# mainboard.net
KiCad netlist of a schematic drawn in EAGLE
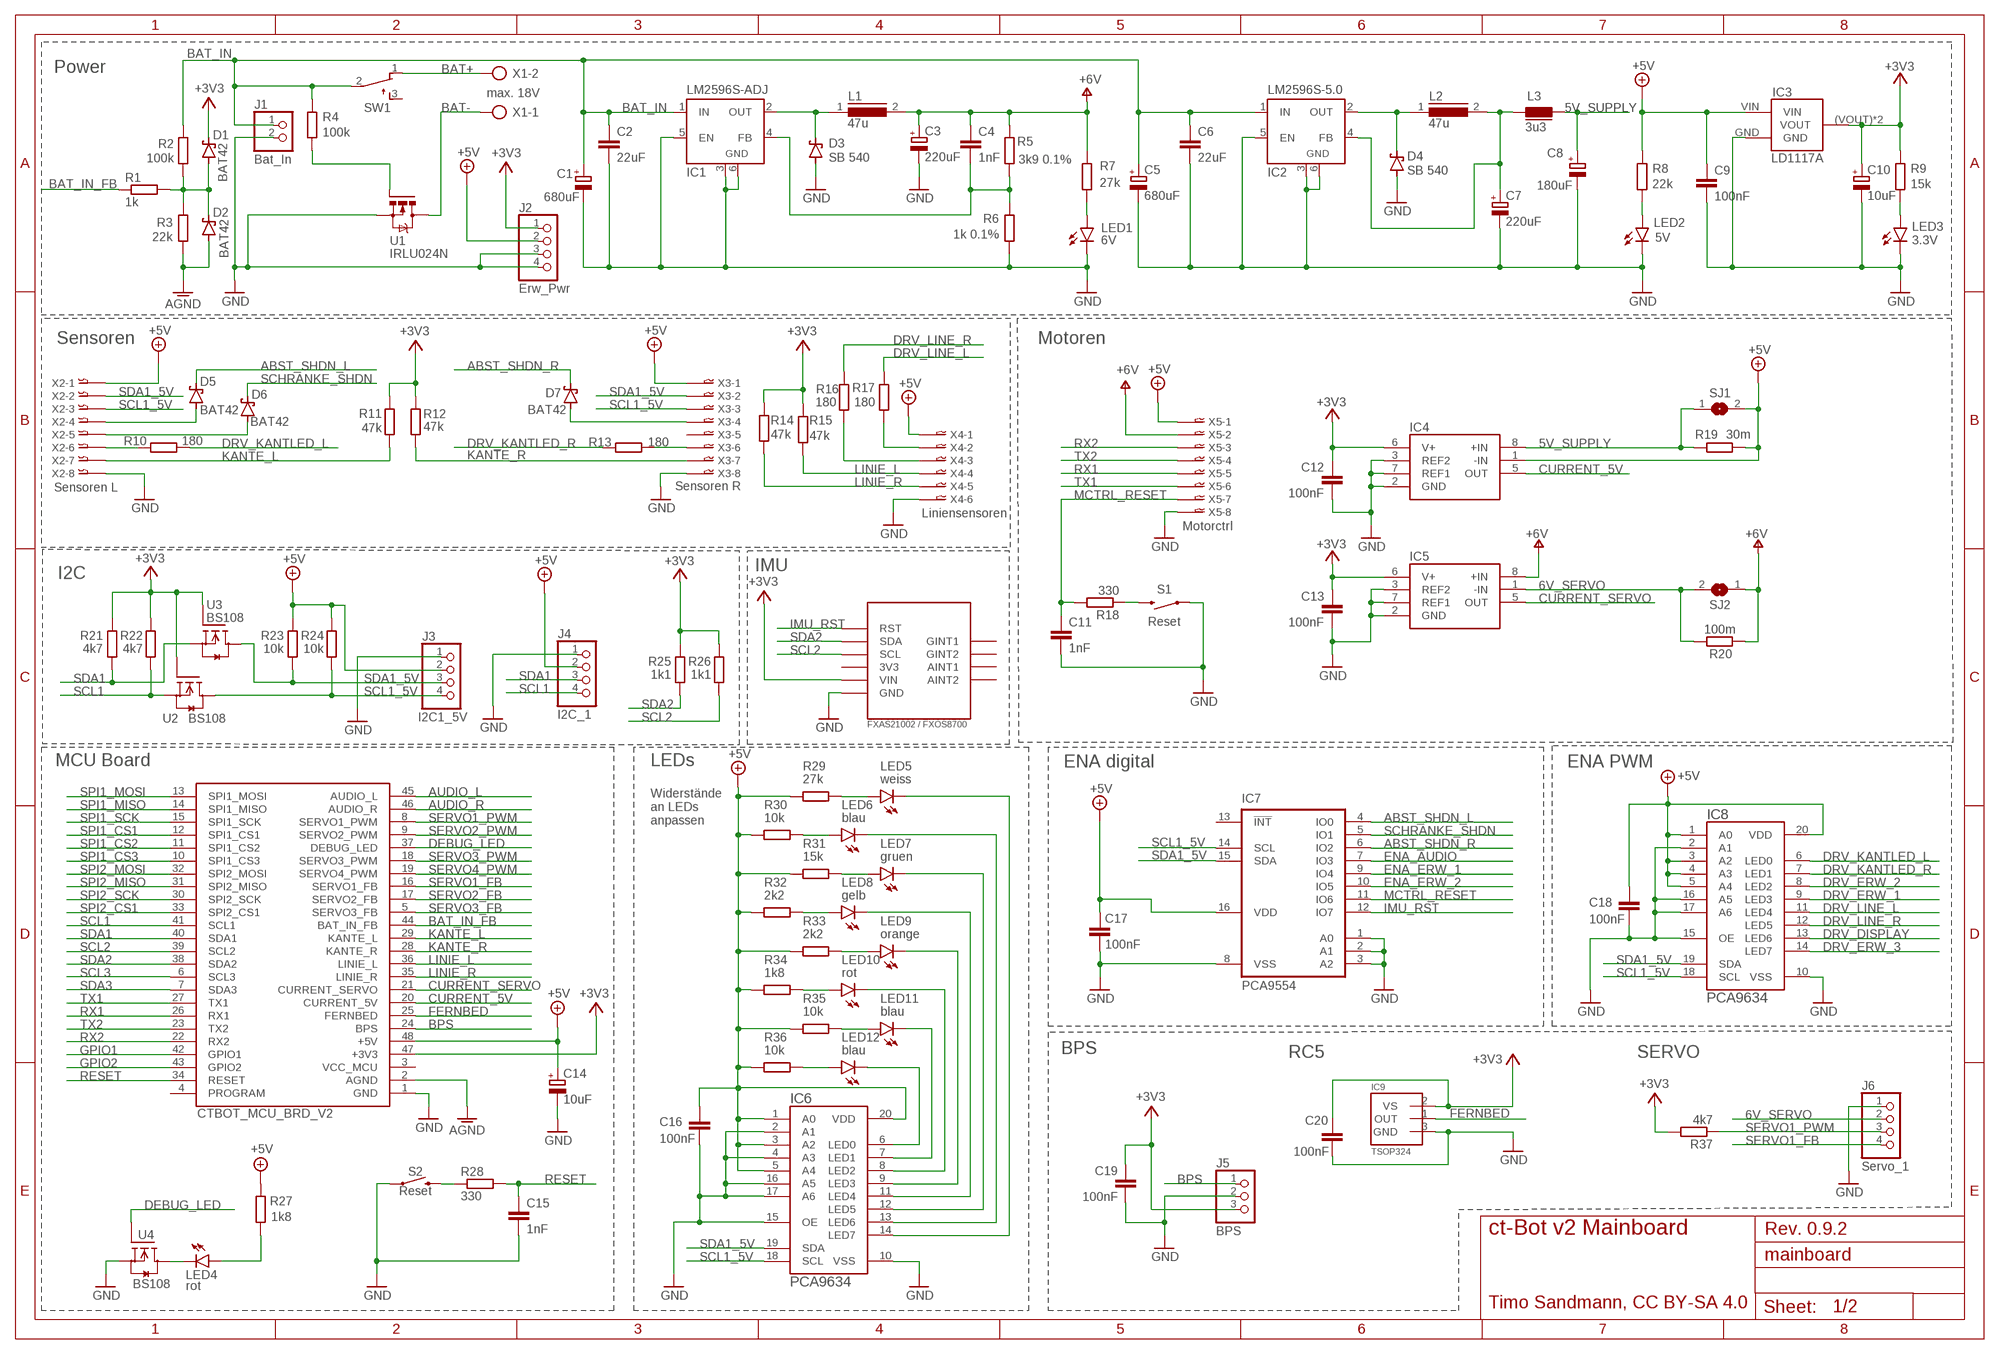
[diagram p0: schematic, sheet 1]
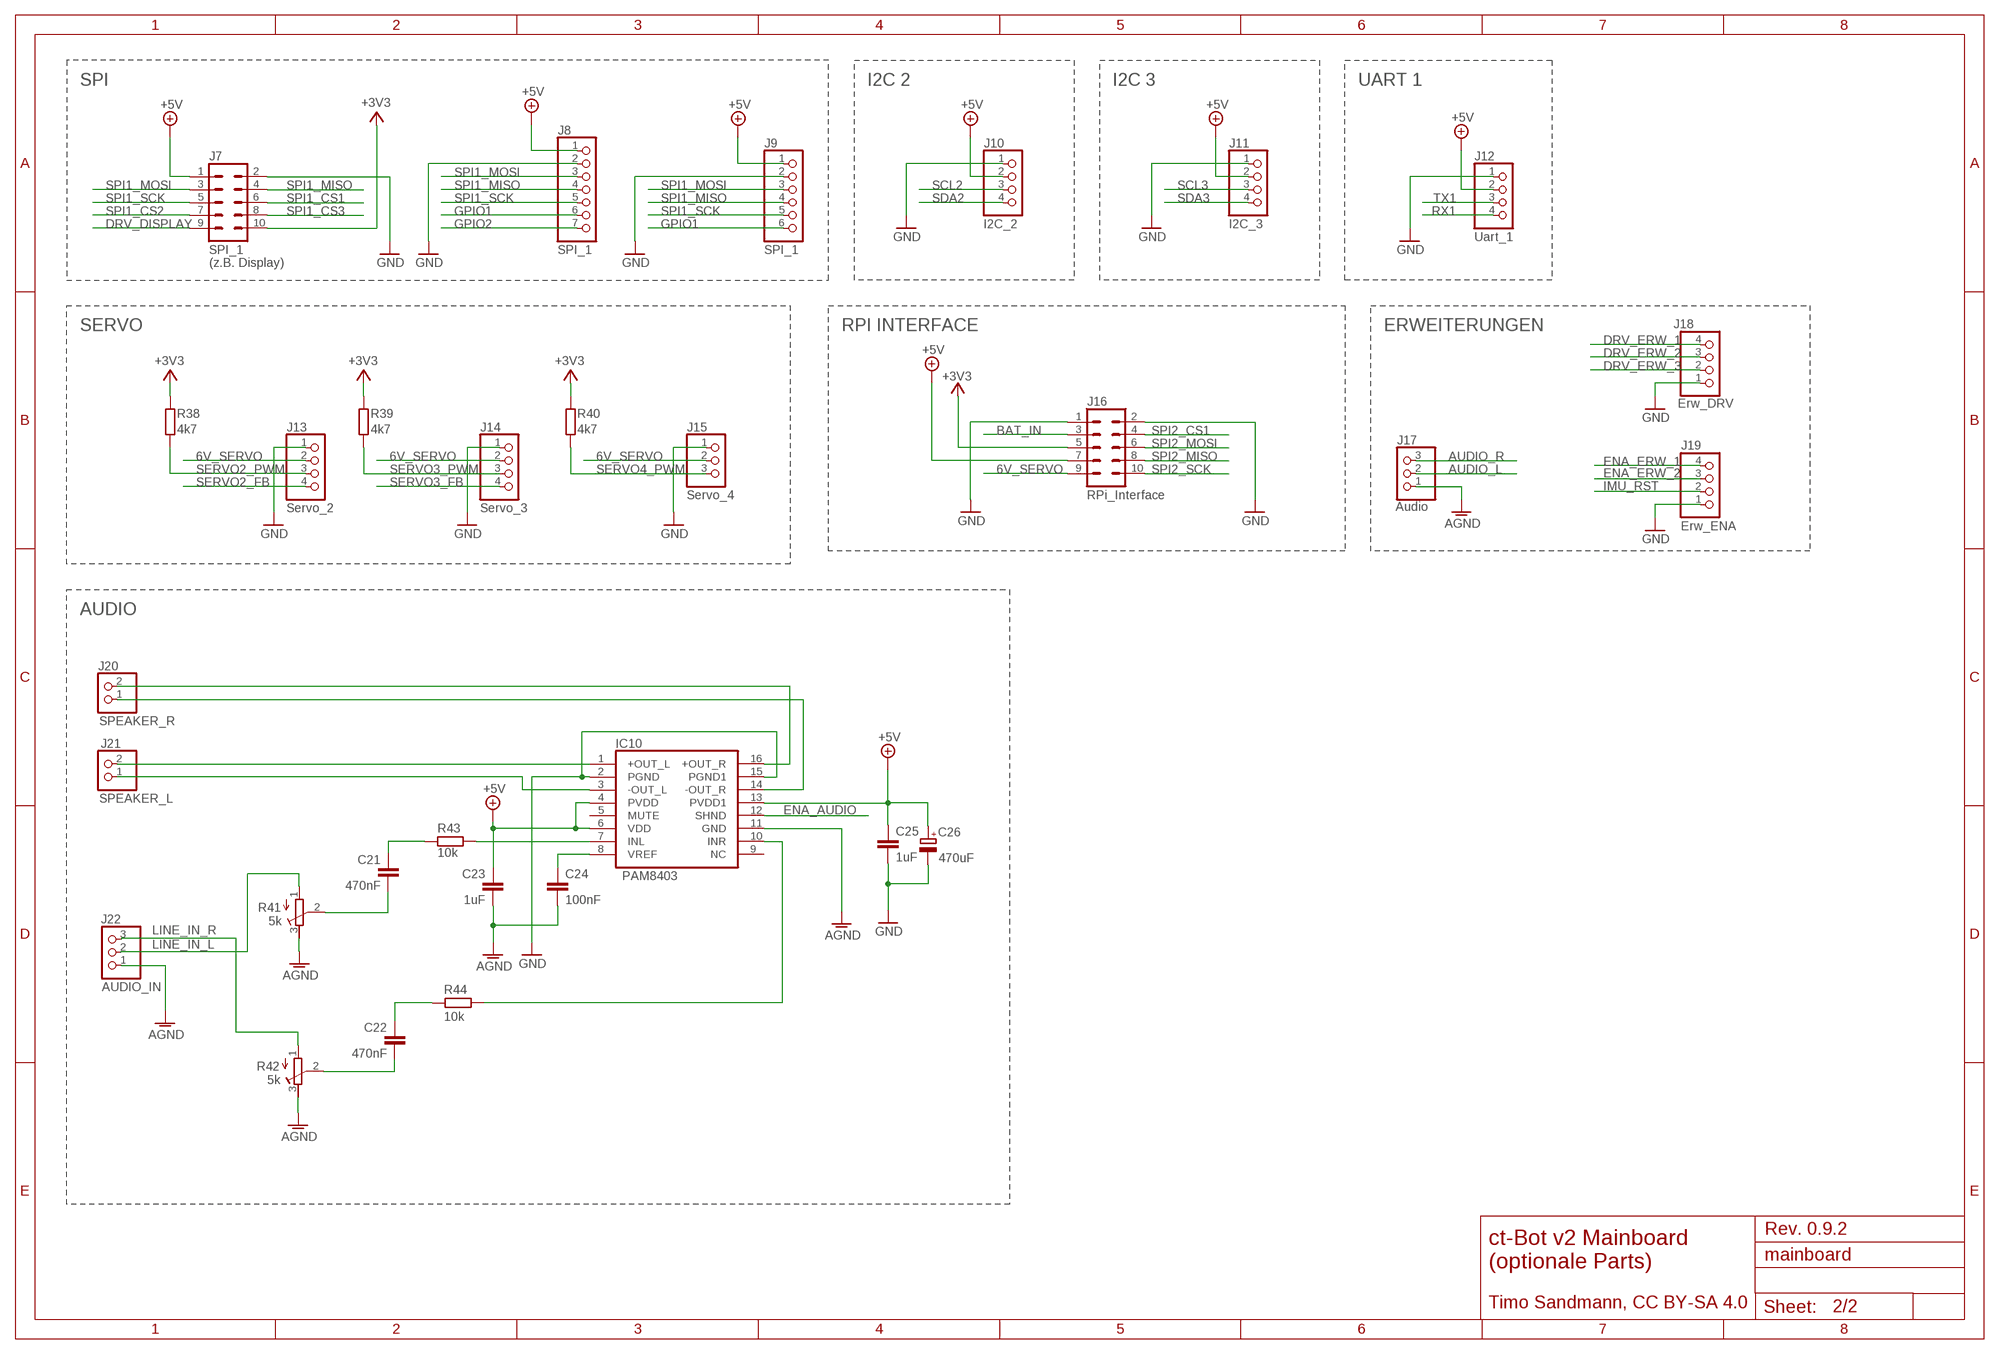
[diagram p1: schematic, sheet 2]

(export (version "E")
  (design (tool "Eeschema 10.0.6"))
  (components
    (comp (ref "C21")
      (value "470nF")
      (footprint "eagle-import:C025-025X050")
      (libsource (lib "eagle-import") (part "C-EU025-025X050"))
    )
    (comp (ref "C22")
      (value "470nF")
      (footprint "eagle-import:C025-025X050")
      (libsource (lib "eagle-import") (part "C-EU025-025X050"))
    )
    (comp (ref "C23")
      (value "1uF")
      (footprint "eagle-import:C025-025X050")
      (libsource (lib "eagle-import") (part "C-EU025-025X050"))
    )
    (comp (ref "C24")
      (value "100nF")
      (footprint "eagle-import:C025-025X050")
      (libsource (lib "eagle-import") (part "C-EU025-025X050"))
    )
    (comp (ref "C25")
      (value "1uF")
      (footprint "eagle-import:C025-025X050")
      (libsource (lib "eagle-import") (part "C-EU025-025X050"))
    )
    (comp (ref "C26")
      (value "470uF")
      (footprint "eagle-import:E3,5-8")
      (libsource (lib "eagle-import") (part "CPOL-EUE3.5-8"))
    )
    (comp (ref "IC10")
      (value "PAM8403")
      (footprint "eagle-import:SOP-16")
      (libsource (lib "eagle-import") (part "PAM8403"))
    )
    (comp (ref "J7")
      (value "SPI_1")
      (footprint "eagle-import:ML10")
      (libsource (lib "eagle-import") (part "ML10"))
    )
    (comp (ref "J8")
      (value "SPI_1")
      (footprint "eagle-import:1X07")
      (libsource (lib "eagle-import") (part "PINHD-1X7"))
    )
    (comp (ref "J9")
      (value "SPI_1")
      (footprint "eagle-import:1X06")
      (libsource (lib "eagle-import") (part "PINHD-1X6"))
    )
    (comp (ref "J10")
      (value "I2C_2")
      (footprint "eagle-import:1X04")
      (libsource (lib "eagle-import") (part "PINHD-1X4"))
    )
    (comp (ref "J11")
      (value "I2C_3")
      (footprint "eagle-import:1X04")
      (libsource (lib "eagle-import") (part "PINHD-1X4"))
    )
    (comp (ref "J12")
      (value "Uart_1")
      (footprint "eagle-import:1X04")
      (libsource (lib "eagle-import") (part "PINHD-1X4"))
    )
    (comp (ref "J13")
      (value "Servo_2")
      (footprint "eagle-import:1X04")
      (libsource (lib "eagle-import") (part "PINHD-1X4"))
    )
    (comp (ref "J14")
      (value "Servo_3")
      (footprint "eagle-import:1X04")
      (libsource (lib "eagle-import") (part "PINHD-1X4"))
    )
    (comp (ref "J15")
      (value "Servo_4")
      (footprint "eagle-import:1X03")
      (libsource (lib "eagle-import") (part "PINHD-1X3"))
    )
    (comp (ref "J16")
      (value "RPi_Interface")
      (footprint "eagle-import:ML10")
      (libsource (lib "eagle-import") (part "ML10"))
    )
    (comp (ref "J17")
      (value "Audio")
      (footprint "eagle-import:1X03")
      (libsource (lib "eagle-import") (part "PINHD-1X3"))
    )
    (comp (ref "J18")
      (value "Erw_DRV")
      (footprint "eagle-import:1X04")
      (libsource (lib "eagle-import") (part "PINHD-1X4"))
    )
    (comp (ref "J19")
      (value "Erw_ENA")
      (footprint "eagle-import:1X04")
      (libsource (lib "eagle-import") (part "PINHD-1X4"))
    )
    (comp (ref "J20")
      (value "SPEAKER_R")
      (footprint "eagle-import:1X02")
      (libsource (lib "eagle-import") (part "PINHD-1X2"))
    )
    (comp (ref "J21")
      (value "SPEAKER_L")
      (footprint "eagle-import:1X02")
      (libsource (lib "eagle-import") (part "PINHD-1X2"))
    )
    (comp (ref "J22")
      (value "AUDIO_IN")
      (footprint "eagle-import:1X03")
      (libsource (lib "eagle-import") (part "PINHD-1X3"))
    )
    (comp (ref "R38")
      (value "4k7")
      (footprint "eagle-import:0204_7")
      (libsource (lib "eagle-import") (part "R-EU_0204/7"))
    )
    (comp (ref "R39")
      (value "4k7")
      (footprint "eagle-import:0204_7")
      (libsource (lib "eagle-import") (part "R-EU_0204/7"))
    )
    (comp (ref "R40")
      (value "4k7")
      (footprint "eagle-import:0204_7")
      (libsource (lib "eagle-import") (part "R-EU_0204/7"))
    )
    (comp (ref "R41")
      (value "5k")
      (footprint "eagle-import:RTRIM64W")
      (libsource (lib "eagle-import") (part "R-TRIMM64W"))
    )
    (comp (ref "R42")
      (value "5k")
      (footprint "eagle-import:RTRIM64W")
      (libsource (lib "eagle-import") (part "R-TRIMM64W"))
    )
    (comp (ref "R43")
      (value "10k")
      (footprint "eagle-import:0204V")
      (libsource (lib "eagle-import") (part "R-EU_0204/2V"))
    )
    (comp (ref "R44")
      (value "10k")
      (footprint "eagle-import:0204V")
      (libsource (lib "eagle-import") (part "R-EU_0204/2V"))
    )
    (comp (ref "C1")
      (value "680uF")
      (footprint "eagle-import:E5-10,5")
      (libsource (lib "eagle-import") (part "CPOL-EUE5-10.5"))
    )
    (comp (ref "C2")
      (value "22uF")
      (footprint "eagle-import:C025-025X050")
      (libsource (lib "eagle-import") (part "C-EU025-025X050"))
    )
    (comp (ref "C3")
      (value "220uF")
      (footprint "eagle-import:E5-10,5")
      (libsource (lib "eagle-import") (part "CPOL-EUE5-10.5"))
    )
    (comp (ref "C4")
      (value "1nF")
      (footprint "eagle-import:C025-025X050")
      (libsource (lib "eagle-import") (part "C-EU025-025X050"))
    )
    (comp (ref "C5")
      (value "680uF")
      (footprint "eagle-import:E5-10,5")
      (libsource (lib "eagle-import") (part "CPOL-EUE5-10.5"))
    )
    (comp (ref "C6")
      (value "22uF")
      (footprint "eagle-import:C025-025X050")
      (libsource (lib "eagle-import") (part "C-EU025-025X050"))
    )
    (comp (ref "C7")
      (value "220uF")
      (footprint "eagle-import:E5-10,5")
      (libsource (lib "eagle-import") (part "CPOL-EUE5-10.5"))
    )
    (comp (ref "C8")
      (value "180uF")
      (footprint "eagle-import:E3,5-8")
      (libsource (lib "eagle-import") (part "CPOL-EUE3.5-8"))
    )
    (comp (ref "C9")
      (value "100nF")
      (footprint "eagle-import:C025-025X050")
      (libsource (lib "eagle-import") (part "C-EU025-025X050"))
    )
    (comp (ref "C10")
      (value "10uF")
      (footprint "eagle-import:E2-5")
      (libsource (lib "eagle-import") (part "CPOL-EUE2-5"))
    )
    (comp (ref "C11")
      (value "1nF")
      (footprint "eagle-import:C025-025X050")
      (libsource (lib "eagle-import") (part "C-EU025-025X050"))
    )
    (comp (ref "C12")
      (value "100nF")
      (footprint "eagle-import:C0805")
      (libsource (lib "eagle-import") (part "C-EUC0805"))
    )
    (comp (ref "C13")
      (value "100nF")
      (footprint "eagle-import:C0805")
      (libsource (lib "eagle-import") (part "C-EUC0805"))
    )
    (comp (ref "C14")
      (value "10uF")
      (footprint "eagle-import:TT2D5L")
      (libsource (lib "eagle-import") (part "CPOL-EUTT2D5L"))
    )
    (comp (ref "C15")
      (value "1nF")
      (footprint "eagle-import:C025-025X050")
      (libsource (lib "eagle-import") (part "C-EU025-025X050"))
    )
    (comp (ref "C16")
      (value "100nF")
      (footprint "eagle-import:C025-025X050")
      (libsource (lib "eagle-import") (part "C-EU025-025X050"))
    )
    (comp (ref "C17")
      (value "100nF")
      (footprint "eagle-import:C025-025X050")
      (libsource (lib "eagle-import") (part "C-EU025-025X050"))
    )
    (comp (ref "C18")
      (value "100nF")
      (footprint "eagle-import:C025-025X050")
      (libsource (lib "eagle-import") (part "C-EU025-025X050"))
    )
    (comp (ref "C19")
      (value "100nF")
      (footprint "eagle-import:C025-025X050")
      (libsource (lib "eagle-import") (part "C-EU025-025X050"))
    )
    (comp (ref "C20")
      (value "100nF")
      (footprint "eagle-import:C025-025X050")
      (libsource (lib "eagle-import") (part "C-EU025-025X050"))
    )
    (comp (ref "D1")
      (value "BAT42")
      (footprint "eagle-import:DO35-7")
      (libsource (lib "eagle-import") (part "BAT42DO35-7"))
    )
    (comp (ref "D2")
      (value "BAT42")
      (footprint "eagle-import:DO35-7")
      (libsource (lib "eagle-import") (part "BAT42DO35-7"))
    )
    (comp (ref "D3")
      (value "SB 540")
      (footprint "eagle-import:DO201T15")
      (libsource (lib "eagle-import") (part "SCHOTTKY-DIODEDO201T15"))
    )
    (comp (ref "D4")
      (value "SB 540")
      (footprint "eagle-import:DO201T15")
      (libsource (lib "eagle-import") (part "SCHOTTKY-DIODEDO201T15"))
    )
    (comp (ref "D5")
      (value "BAT42")
      (footprint "eagle-import:0207_2V")
      (libsource (lib "eagle-import") (part "BAT42{dblquote}"))
    )
    (comp (ref "D6")
      (value "BAT42")
      (footprint "eagle-import:0207_2V")
      (libsource (lib "eagle-import") (part "BAT42{dblquote}"))
    )
    (comp (ref "D7")
      (value "BAT42")
      (footprint "eagle-import:0207_2V")
      (libsource (lib "eagle-import") (part "BAT42{dblquote}"))
    )
    (comp (ref "IC1")
      (value "LM2596S-ADJ")
      (footprint "eagle-import:TO263-5")
      (libsource (lib "eagle-import") (part "LM2596S"))
    )
    (comp (ref "IC2")
      (value "LM2596S-5.0")
      (footprint "eagle-import:TO263-5")
      (libsource (lib "eagle-import") (part "LM2596S"))
    )
    (comp (ref "IC3")
      (value "LD1117A")
      (footprint "eagle-import:LD1117SOT-223")
      (libsource (lib "eagle-import") (part "LD1117"))
    )
    (comp (ref "IC4")
      (value "INA28AID")
      (footprint "eagle-import:SO08")
      (fields (field (name "MF") "TEXAS INSTRUMENTS"))
      (libsource (lib "eagle-import") (part "INA28AID"))
    )
    (comp (ref "IC5")
      (value "INA28AID")
      (footprint "eagle-import:SO08")
      (fields (field (name "MF") "TEXAS INSTRUMENTS"))
      (libsource (lib "eagle-import") (part "INA28AID"))
    )
    (comp (ref "IC6")
      (value "PCA9634")
      (footprint "eagle-import:SO20W")
      (libsource (lib "eagle-import") (part "PCA9634-SO20"))
    )
    (comp (ref "IC7")
      (value "PCA9554")
      (footprint "eagle-import:SO16W")
      (libsource (lib "eagle-import") (part "PCA9554D"))
    )
    (comp (ref "IC8")
      (value "PCA9634")
      (footprint "eagle-import:SO20W")
      (libsource (lib "eagle-import") (part "PCA9634-SO20"))
    )
    (comp (ref "IC9")
      (value "TSOP324")
      (footprint "eagle-import:TSOP324")
      (libsource (lib "eagle-import") (part "TSOP324"))
    )
    (comp (ref "J1")
      (value "Bat_In")
      (footprint "eagle-import:1X02")
      (libsource (lib "eagle-import") (part "PINHD-1X2"))
    )
    (comp (ref "J2")
      (value "Erw_Pwr")
      (footprint "eagle-import:1X04")
      (libsource (lib "eagle-import") (part "PINHD-1X4"))
    )
    (comp (ref "J3")
      (value "I2C1_5V")
      (footprint "eagle-import:1X04")
      (libsource (lib "eagle-import") (part "PINHD-1X4"))
    )
    (comp (ref "J4")
      (value "I2C_1")
      (footprint "eagle-import:1X04")
      (libsource (lib "eagle-import") (part "PINHD-1X4"))
    )
    (comp (ref "J5")
      (value "BPS")
      (footprint "eagle-import:1X03")
      (libsource (lib "eagle-import") (part "PINHD-1X3"))
    )
    (comp (ref "J6")
      (value "Servo_1")
      (footprint "eagle-import:1X04")
      (libsource (lib "eagle-import") (part "PINHD-1X4"))
    )
    (comp (ref "L1")
      (value "47u")
      (footprint "eagle-import:09HCP")
      (libsource (lib "eagle-import") (part "INDUCTOR_09HCP"))
    )
    (comp (ref "L2")
      (value "47u")
      (footprint "eagle-import:09HCP")
      (libsource (lib "eagle-import") (part "INDUCTOR_09HCP"))
    )
    (comp (ref "L3")
      (value "3u3")
      (footprint "eagle-import:FASTRON_07HCP_INDUCTOR")
      (libsource (lib "eagle-import") (part "07HCP-3U3"))
    )
    (comp (ref "LED1")
      (value "6V")
      (footprint "eagle-import:LED3MM")
      (libsource (lib "eagle-import") (part "LED3MM"))
    )
    (comp (ref "LED2")
      (value "5V")
      (footprint "eagle-import:LED3MM")
      (libsource (lib "eagle-import") (part "LED3MM"))
    )
    (comp (ref "LED3")
      (value "3.3V")
      (footprint "eagle-import:LED3MM")
      (libsource (lib "eagle-import") (part "LED3MM"))
    )
    (comp (ref "LED4")
      (value "rot")
      (footprint "eagle-import:LED3MM")
      (libsource (lib "eagle-import") (part "LED3MM"))
    )
    (comp (ref "LED5")
      (value "weiss")
      (footprint "eagle-import:LED3MM")
      (libsource (lib "eagle-import") (part "LED3MM"))
    )
    (comp (ref "LED6")
      (value "blau")
      (footprint "eagle-import:LED3MM")
      (libsource (lib "eagle-import") (part "LED3MM"))
    )
    (comp (ref "LED7")
      (value "gruen")
      (footprint "eagle-import:LED3MM")
      (libsource (lib "eagle-import") (part "LED3MM"))
    )
    (comp (ref "LED8")
      (value "gelb")
      (footprint "eagle-import:LED3MM")
      (libsource (lib "eagle-import") (part "LED3MM"))
    )
    (comp (ref "LED9")
      (value "orange")
      (footprint "eagle-import:LED3MM")
      (libsource (lib "eagle-import") (part "LED3MM"))
    )
    (comp (ref "LED10")
      (value "rot")
      (footprint "eagle-import:LED3MM")
      (libsource (lib "eagle-import") (part "LED3MM"))
    )
    (comp (ref "LED11")
      (value "blau")
      (footprint "eagle-import:LED3MM")
      (libsource (lib "eagle-import") (part "LED3MM"))
    )
    (comp (ref "LED12")
      (value "blau")
      (footprint "eagle-import:LED3MM")
      (libsource (lib "eagle-import") (part "LED3MM"))
    )
    (comp (ref "MCU")
      (value "CTBOT_MCU_BRD_V2")
      (footprint "eagle-import:DIP48")
      (libsource (lib "eagle-import") (part "CTBOT_MCU_BRD_V2"))
    )
    (comp (ref "R1")
      (value "1k")
      (footprint "eagle-import:0204_7")
      (libsource (lib "eagle-import") (part "R-EU_0204/7"))
    )
    (comp (ref "R2")
      (value "100k")
      (footprint "eagle-import:0204_7")
      (libsource (lib "eagle-import") (part "R-EU_0204/7"))
    )
    (comp (ref "R3")
      (value "22k")
      (footprint "eagle-import:0204_7")
      (libsource (lib "eagle-import") (part "R-EU_0204/7"))
    )
    (comp (ref "R4")
      (value "100k")
      (footprint "eagle-import:0204V")
      (libsource (lib "eagle-import") (part "R-EU_0204/2V"))
    )
    (comp (ref "R5")
      (value "3k9 0.1%")
      (footprint "eagle-import:0204V")
      (libsource (lib "eagle-import") (part "R-EU_0204/2V"))
    )
    (comp (ref "R6")
      (value "1k 0.1%")
      (footprint "eagle-import:0204V")
      (libsource (lib "eagle-import") (part "R-EU_0204/2V"))
    )
    (comp (ref "R7")
      (value "27k")
      (footprint "eagle-import:0204V")
      (libsource (lib "eagle-import") (part "R-EU_0204/2V"))
    )
    (comp (ref "R8")
      (value "22k")
      (footprint "eagle-import:0204V")
      (libsource (lib "eagle-import") (part "R-EU_0204/2V"))
    )
    (comp (ref "R9")
      (value "15k")
      (footprint "eagle-import:0204V")
      (libsource (lib "eagle-import") (part "R-EU_0204/2V"))
    )
    (comp (ref "R10")
      (value "180")
      (footprint "eagle-import:0204V")
      (libsource (lib "eagle-import") (part "R-EU_0204/2V"))
    )
    (comp (ref "R11")
      (value "47k")
      (footprint "eagle-import:0204V")
      (libsource (lib "eagle-import") (part "R-EU_0204/2V"))
    )
    (comp (ref "R12")
      (value "47k")
      (footprint "eagle-import:0204V")
      (libsource (lib "eagle-import") (part "R-EU_0204/2V"))
    )
    (comp (ref "R13")
      (value "180")
      (footprint "eagle-import:0204V")
      (libsource (lib "eagle-import") (part "R-EU_0204/2V"))
    )
    (comp (ref "R14")
      (value "47k")
      (footprint "eagle-import:0204_7")
      (libsource (lib "eagle-import") (part "R-EU_0204/7"))
    )
    (comp (ref "R15")
      (value "47k")
      (footprint "eagle-import:0204_7")
      (libsource (lib "eagle-import") (part "R-EU_0204/7"))
    )
    (comp (ref "R16")
      (value "180")
      (footprint "eagle-import:0204V")
      (libsource (lib "eagle-import") (part "R-EU_0204/2V"))
    )
    (comp (ref "R17")
      (value "180")
      (footprint "eagle-import:0204V")
      (libsource (lib "eagle-import") (part "R-EU_0204/2V"))
    )
    (comp (ref "R18")
      (value "330")
      (footprint "eagle-import:0204V")
      (libsource (lib "eagle-import") (part "R-EU_0204/2V"))
    )
    (comp (ref "R19")
      (value "30m")
      (footprint "eagle-import:R2512")
      (libsource (lib "eagle-import") (part "R-EU_R2512"))
    )
    (comp (ref "R20")
      (value "100m")
      (footprint "eagle-import:R2512")
      (libsource (lib "eagle-import") (part "R-EU_R2512"))
    )
    (comp (ref "R21")
      (value "4k7")
      (footprint "eagle-import:0204_7")
      (libsource (lib "eagle-import") (part "R-EU_0204/7"))
    )
    (comp (ref "R22")
      (value "4k7")
      (footprint "eagle-import:0204_7")
      (libsource (lib "eagle-import") (part "R-EU_0204/7"))
    )
    (comp (ref "R23")
      (value "10k")
      (footprint "eagle-import:0204V")
      (libsource (lib "eagle-import") (part "R-EU_0204/2V"))
    )
    (comp (ref "R24")
      (value "10k")
      (footprint "eagle-import:0204V")
      (libsource (lib "eagle-import") (part "R-EU_0204/2V"))
    )
    (comp (ref "R25")
      (value "1k1")
      (footprint "eagle-import:0204_7")
      (libsource (lib "eagle-import") (part "R-EU_0204/7"))
    )
    (comp (ref "R26")
      (value "1k1")
      (footprint "eagle-import:0204_7")
      (libsource (lib "eagle-import") (part "R-EU_0204/7"))
    )
    (comp (ref "R27")
      (value "1k8")
      (footprint "eagle-import:0204V")
      (libsource (lib "eagle-import") (part "R-EU_0204/2V"))
    )
    (comp (ref "R28")
      (value "330")
      (footprint "eagle-import:0204V")
      (libsource (lib "eagle-import") (part "R-EU_0204/2V"))
    )
    (comp (ref "R29")
      (value "27k")
      (footprint "eagle-import:0204V")
      (libsource (lib "eagle-import") (part "R-EU_0204/2V"))
    )
    (comp (ref "R30")
      (value "10k")
      (footprint "eagle-import:0204V")
      (libsource (lib "eagle-import") (part "R-EU_0204/2V"))
    )
    (comp (ref "R31")
      (value "15k")
      (footprint "eagle-import:0204V")
      (libsource (lib "eagle-import") (part "R-EU_0204/2V"))
    )
    (comp (ref "R32")
      (value "2k2")
      (footprint "eagle-import:0204V")
      (libsource (lib "eagle-import") (part "R-EU_0204/2V"))
    )
    (comp (ref "R33")
      (value "2k2")
      (footprint "eagle-import:0204V")
      (libsource (lib "eagle-import") (part "R-EU_0204/2V"))
    )
    (comp (ref "R34")
      (value "1k8")
      (footprint "eagle-import:0204V")
      (libsource (lib "eagle-import") (part "R-EU_0204/2V"))
    )
    (comp (ref "R35")
      (value "10k")
      (footprint "eagle-import:0204V")
      (libsource (lib "eagle-import") (part "R-EU_0204/2V"))
    )
    (comp (ref "R36")
      (value "10k")
      (footprint "eagle-import:0204V")
      (libsource (lib "eagle-import") (part "R-EU_0204/2V"))
    )
    (comp (ref "R37")
      (value "4k7")
      (footprint "eagle-import:0204_7")
      (libsource (lib "eagle-import") (part "R-EU_0204/7"))
    )
    (comp (ref "S1")
      (value "Reset")
      (footprint "eagle-import:TACTILE_SWITCH_PTH_6.0MM")
      (libsource (lib "eagle-import") (part "MOMENTARY-SWITCH-SPST-PTH-6.0MM"))
    )
    (comp (ref "S2")
      (value "Reset")
      (footprint "eagle-import:TACTILE_SWITCH_PTH_6.0MM")
      (libsource (lib "eagle-import") (part "MOMENTARY-SWITCH-SPST-PTH-6.0MM"))
    )
    (comp (ref "SJ1") (value "SJ") (footprint "eagle-import:SJ") (libsource (lib "eagle-import") (part "SJ")))
    (comp (ref "SJ2") (value "SJ") (footprint "eagle-import:SJ") (libsource (lib "eagle-import") (part "SJ")))
    (comp (ref "SW1")
      (value "TL32PO")
      (footprint "eagle-import:TL3XPO")
      (libsource (lib "eagle-import") (part "TL32PO"))
    )
    (comp (ref "U$10")
      (value "IMU")
      (footprint "eagle-import:NXP_9DOF")
      (libsource (lib "eagle-import") (part "NXP_9DOF"))
    )
    (comp (ref "U1")
      (value "IRLU024N")
      (footprint "eagle-import:TO251AA")
      (libsource (lib "eagle-import") (part "IRLU024NTO-251AA"))
    )
    (comp (ref "U2")
      (value "BS108")
      (footprint "eagle-import:SOT54E")
      (libsource (lib "eagle-import") (part "BS108"))
    )
    (comp (ref "U3")
      (value "BS108")
      (footprint "eagle-import:SOT54E")
      (libsource (lib "eagle-import") (part "BS108"))
    )
    (comp (ref "U4")
      (value "BS108")
      (footprint "eagle-import:SOT54E")
      (libsource (lib "eagle-import") (part "BS108"))
    )
    (comp (ref "X1")
      (value "max. 18V")
      (footprint "eagle-import:AK500_2-H")
      (libsource (lib "eagle-import") (part "SCHRAUBKLEMME/2"))
    )
    (comp (ref "X2")
      (value "Sensoren L")
      (footprint "eagle-import:B8B-XH")
      (libsource (lib "eagle-import") (part "08-JST"))
    )
    (comp (ref "X3")
      (value "Sensoren R")
      (footprint "eagle-import:B8B-XH")
      (libsource (lib "eagle-import") (part "08-JST"))
    )
    (comp (ref "X4")
      (value "Liniensensoren")
      (footprint "eagle-import:B6B-XH")
      (libsource (lib "eagle-import") (part "06-JST-B6B-XH-A"))
    )
    (comp (ref "X5")
      (value "Motorctrl")
      (footprint "eagle-import:B8B-XH")
      (libsource (lib "eagle-import") (part "08-JST"))
    )
  )
  (nets
    (net (code "1") (name "+3V3") (class "Default")
      (node (ref "C10") (pin "+") (pinfunction "+_+") (pintype "passive"))
      (node (ref "C12") (pin "1") (pinfunction "1_1") (pintype "passive"))
      (node (ref "C13") (pin "1") (pinfunction "1_1") (pintype "passive"))
      (node (ref "C19") (pin "1") (pinfunction "1_1") (pintype "passive"))
      (node (ref "C20") (pin "1") (pinfunction "1_1") (pintype "passive"))
      (node (ref "D1") (pin "C") (pinfunction "C_C") (pintype "passive"))
      (node (ref "IC3") (pin "(VOUT)") (pinfunction "VOUT_(VOUT)") (pintype "bidirectional"))
      (node (ref "IC3") (pin "VOUT") (pinfunction "VOUT_VOUT") (pintype "bidirectional"))
      (node (ref "IC4") (pin "6") (pinfunction "V+_6") (pintype "power_in"))
      (node (ref "IC5") (pin "6") (pinfunction "V+_6") (pintype "power_in"))
      (node (ref "IC9") (pin "2") (pinfunction "VS_2") (pintype "power_in"))
      (node (ref "J16") (pin "5") (pinfunction "5_5") (pintype "passive"))
      (node (ref "J2") (pin "1") (pinfunction "1_1") (pintype "passive"))
      (node (ref "J5") (pin "3") (pinfunction "3_3") (pintype "passive"))
      (node (ref "J7") (pin "10") (pinfunction "10_10") (pintype "passive"))
      (node (ref "MCU") (pin "47") (pinfunction "+3V3_47") (pintype "power_in"))
      (node (ref "R11") (pin "2") (pinfunction "2_2") (pintype "passive"))
      (node (ref "R12") (pin "1") (pinfunction "1_1") (pintype "passive"))
      (node (ref "R14") (pin "2") (pinfunction "2_2") (pintype "passive"))
      (node (ref "R15") (pin "2") (pinfunction "2_2") (pintype "passive"))
      (node (ref "R21") (pin "2") (pinfunction "2_2") (pintype "passive"))
      (node (ref "R22") (pin "2") (pinfunction "2_2") (pintype "passive"))
      (node (ref "R25") (pin "2") (pinfunction "2_2") (pintype "passive"))
      (node (ref "R26") (pin "2") (pinfunction "2_2") (pintype "passive"))
      (node (ref "R37") (pin "2") (pinfunction "2_2") (pintype "passive"))
      (node (ref "R38") (pin "2") (pinfunction "2_2") (pintype "passive"))
      (node (ref "R39") (pin "2") (pinfunction "2_2") (pintype "passive"))
      (node (ref "R40") (pin "2") (pinfunction "2_2") (pintype "passive"))
      (node (ref "R9") (pin "2") (pinfunction "2_2") (pintype "passive"))
      (node (ref "U$10") (pin "VIN") (pinfunction "VIN_VIN") (pintype "power_in"))
      (node (ref "U2") (pin "G") (pinfunction "G_G") (pintype "passive"))
      (node (ref "U3") (pin "G") (pinfunction "G_G") (pintype "passive"))
    )
    (net (code "2") (name "+5V") (class "Default")
      (node (ref "C14") (pin "+") (pinfunction "+_+") (pintype "passive"))
      (node (ref "C16") (pin "1") (pinfunction "1_1") (pintype "passive"))
      (node (ref "C17") (pin "1") (pinfunction "1_1") (pintype "passive"))
      (node (ref "C18") (pin "1") (pinfunction "1_1") (pintype "passive"))
      (node (ref "C23") (pin "1") (pinfunction "1_1") (pintype "passive"))
      (node (ref "C25") (pin "1") (pinfunction "1_1") (pintype "passive"))
      (node (ref "C26") (pin "+") (pinfunction "+_+") (pintype "passive"))
      (node (ref "C9") (pin "1") (pinfunction "1_1") (pintype "passive"))
      (node (ref "IC10") (pin "13") (pinfunction "PVDD1_13") (pintype "power_in"))
      (node (ref "IC10") (pin "4") (pinfunction "PVDD_4") (pintype "power_in"))
      (node (ref "IC10") (pin "6") (pinfunction "VDD_6") (pintype "power_in"))
      (node (ref "IC3") (pin "VIN") (pinfunction "VIN_VIN") (pintype "bidirectional"))
      (node (ref "IC4") (pin "1") (pinfunction "-IN_1") (pintype "input"))
      (node (ref "IC6") (pin "1") (pinfunction "A0_1") (pintype "input"))
      (node (ref "IC6") (pin "20") (pinfunction "VDD_20") (pintype "power_in"))
      (node (ref "IC6") (pin "3") (pinfunction "A2_3") (pintype "input"))
      (node (ref "IC6") (pin "5") (pinfunction "A4_5") (pintype "input"))
      (node (ref "IC7") (pin "16") (pinfunction "VDD_16") (pintype "power_in"))
      (node (ref "IC8") (pin "1") (pinfunction "A0_1") (pintype "input"))
      (node (ref "IC8") (pin "20") (pinfunction "VDD_20") (pintype "power_in"))
      (node (ref "IC8") (pin "3") (pinfunction "A2_3") (pintype "input"))
      (node (ref "IC8") (pin "4") (pinfunction "A3_4") (pintype "input"))
      (node (ref "IC8") (pin "5") (pinfunction "A4_5") (pintype "input"))
      (node (ref "J10") (pin "2") (pinfunction "2_2") (pintype "passive"))
      (node (ref "J11") (pin "2") (pinfunction "2_2") (pintype "passive"))
      (node (ref "J12") (pin "2") (pinfunction "2_2") (pintype "passive"))
      (node (ref "J16") (pin "7") (pinfunction "7_7") (pintype "passive"))
      (node (ref "J2") (pin "2") (pinfunction "2_2") (pintype "passive"))
      (node (ref "J3") (pin "2") (pinfunction "2_2") (pintype "passive"))
      (node (ref "J4") (pin "2") (pinfunction "2_2") (pintype "passive"))
      (node (ref "J7") (pin "1") (pinfunction "1_1") (pintype "passive"))
      (node (ref "J8") (pin "1") (pinfunction "1_1") (pintype "passive"))
      (node (ref "J9") (pin "1") (pinfunction "1_1") (pintype "passive"))
      (node (ref "MCU") (pin "48") (pinfunction "+5V_48") (pintype "power_in"))
      (node (ref "R19") (pin "2") (pinfunction "2_2") (pintype "passive"))
      (node (ref "R23") (pin "2") (pinfunction "2_2") (pintype "passive"))
      (node (ref "R24") (pin "2") (pinfunction "2_2") (pintype "passive"))
      (node (ref "R27") (pin "2") (pinfunction "2_2") (pintype "passive"))
      (node (ref "R29") (pin "1") (pinfunction "1_1") (pintype "passive"))
      (node (ref "R30") (pin "1") (pinfunction "1_1") (pintype "passive"))
      (node (ref "R31") (pin "1") (pinfunction "1_1") (pintype "passive"))
      (node (ref "R32") (pin "1") (pinfunction "1_1") (pintype "passive"))
      (node (ref "R33") (pin "1") (pinfunction "1_1") (pintype "passive"))
      (node (ref "R34") (pin "1") (pinfunction "1_1") (pintype "passive"))
      (node (ref "R35") (pin "1") (pinfunction "1_1") (pintype "passive"))
      (node (ref "R36") (pin "1") (pinfunction "1_1") (pintype "passive"))
      (node (ref "R8") (pin "2") (pinfunction "2_2") (pintype "passive"))
      (node (ref "SJ1") (pin "2") (pinfunction "2_2") (pintype "passive"))
      (node (ref "X2") (pin "P$1") (pinfunction "1_P$1") (pintype "passive"))
      (node (ref "X3") (pin "P$1") (pinfunction "1_P$1") (pintype "passive"))
      (node (ref "X4") (pin "P$1") (pinfunction "1_P$1") (pintype "passive"))
      (node (ref "X5") (pin "P$1") (pinfunction "1_P$1") (pintype "passive"))
    )
    (net (code "3") (name "+6V") (class "Default")
      (node (ref "C3") (pin "+") (pinfunction "+_+") (pintype "passive"))
      (node (ref "C4") (pin "1") (pinfunction "1_1") (pintype "passive"))
      (node (ref "IC5") (pin "8") (pinfunction "+IN_8") (pintype "input"))
      (node (ref "L1") (pin "2") (pinfunction "2_2") (pintype "passive"))
      (node (ref "R20") (pin "1") (pinfunction "1_1") (pintype "passive"))
      (node (ref "R5") (pin "2") (pinfunction "2_2") (pintype "passive"))
      (node (ref "R7") (pin "1") (pinfunction "1_1") (pintype "passive"))
      (node (ref "SJ2") (pin "1") (pinfunction "1_1") (pintype "passive"))
      (node (ref "X5") (pin "P$2") (pinfunction "1_P$2") (pintype "passive"))
    )
    (net (code "4") (name "5V_SUPPLY") (class "Default")
      (node (ref "C8") (pin "+") (pinfunction "+_+") (pintype "passive"))
      (node (ref "IC4") (pin "8") (pinfunction "+IN_8") (pintype "input"))
      (node (ref "L3") (pin "2") (pinfunction "2_2") (pintype "passive"))
      (node (ref "R19") (pin "1") (pinfunction "1_1") (pintype "passive"))
      (node (ref "SJ1") (pin "1") (pinfunction "1_1") (pintype "passive"))
    )
    (net (code "5") (name "6V_SERVO") (class "Default")
      (node (ref "IC5") (pin "1") (pinfunction "-IN_1") (pintype "input"))
      (node (ref "J13") (pin "2") (pinfunction "2_2") (pintype "passive"))
      (node (ref "J14") (pin "2") (pinfunction "2_2") (pintype "passive"))
      (node (ref "J15") (pin "2") (pinfunction "2_2") (pintype "passive"))
      (node (ref "J16") (pin "9") (pinfunction "9_9") (pintype "passive"))
      (node (ref "J6") (pin "2") (pinfunction "2_2") (pintype "passive"))
      (node (ref "R20") (pin "2") (pinfunction "2_2") (pintype "passive"))
      (node (ref "SJ2") (pin "2") (pinfunction "2_2") (pintype "passive"))
    )
    (net (code "6") (name "ABST_SHDN_L") (class "Default")
      (node (ref "D5") (pin "2") (pinfunction "C_2") (pintype "passive"))
      (node (ref "IC7") (pin "4") (pinfunction "IO0_4") (pintype "bidirectional"))
    )
    (net (code "7") (name "ABST_SHDN_R") (class "Default")
      (node (ref "D7") (pin "2") (pinfunction "C_2") (pintype "passive"))
      (node (ref "IC7") (pin "6") (pinfunction "IO2_6") (pintype "bidirectional"))
    )
    (net (code "8") (name "AGND") (class "Default")
      (node (ref "C23") (pin "2") (pinfunction "2_2") (pintype "passive"))
      (node (ref "C24") (pin "2") (pinfunction "2_2") (pintype "passive"))
      (node (ref "D2") (pin "A") (pinfunction "A_A") (pintype "passive"))
      (node (ref "IC10") (pin "11") (pinfunction "GND_11") (pintype "power_in"))
      (node (ref "J17") (pin "1") (pinfunction "1_1") (pintype "passive"))
      (node (ref "J22") (pin "1") (pinfunction "1_1") (pintype "passive"))
      (node (ref "MCU") (pin "2") (pinfunction "AGND_2") (pintype "power_in"))
      (node (ref "R3") (pin "1") (pinfunction "1_1") (pintype "passive"))
      (node (ref "R41") (pin "3") (pinfunction "E_3") (pintype "passive"))
      (node (ref "R42") (pin "3") (pinfunction "E_3") (pintype "passive"))
    )
    (net (code "9") (name "AUDIO_L") (class "Default")
      (node (ref "J17") (pin "2") (pinfunction "2_2") (pintype "passive"))
      (node (ref "MCU") (pin "45") (pinfunction "AUDIO_L_45") (pintype "output"))
    )
    (net (code "10") (name "AUDIO_R") (class "Default")
      (node (ref "J17") (pin "3") (pinfunction "3_3") (pintype "passive"))
      (node (ref "MCU") (pin "46") (pinfunction "AUDIO_R_46") (pintype "output"))
    )
    (net (code "11") (name "BAT+") (class "Default")
      (node (ref "SW1") (pin "1") (pinfunction "O_1") (pintype "passive"))
      (node (ref "X1") (pin "2") (pinfunction "KL_2") (pintype "passive"))
    )
    (net (code "12") (name "BAT-") (class "Default")
      (node (ref "U1") (pin "2") (pinfunction "D_2") (pintype "passive"))
      (node (ref "U1") (pin "4") (pinfunction "D_4") (pintype "passive"))
      (node (ref "X1") (pin "1") (pinfunction "KL_1") (pintype "passive"))
    )
    (net (code "13") (name "BAT_IN") (class "Default")
      (node (ref "C1") (pin "+") (pinfunction "+_+") (pintype "passive"))
      (node (ref "C2") (pin "1") (pinfunction "1_1") (pintype "passive"))
      (node (ref "C5") (pin "+") (pinfunction "+_+") (pintype "passive"))
      (node (ref "C6") (pin "1") (pinfunction "1_1") (pintype "passive"))
      (node (ref "IC1") (pin "1") (pinfunction "IN_1") (pintype "input"))
      (node (ref "IC2") (pin "1") (pinfunction "IN_1") (pintype "input"))
      (node (ref "J1") (pin "1") (pinfunction "1_1") (pintype "passive"))
      (node (ref "J16") (pin "3") (pinfunction "3_3") (pintype "passive"))
      (node (ref "R2") (pin "2") (pinfunction "2_2") (pintype "passive"))
      (node (ref "R4") (pin "2") (pinfunction "2_2") (pintype "passive"))
      (node (ref "SW1") (pin "2") (pinfunction "P_2") (pintype "passive"))
    )
    (net (code "14") (name "BAT_IN_FB") (class "Default")
      (node (ref "MCU") (pin "44") (pinfunction "BAT_IN_FB_44") (pintype "input"))
      (node (ref "R1") (pin "1") (pinfunction "1_1") (pintype "passive"))
    )
    (net (code "15") (name "BPS") (class "Default")
      (node (ref "J5") (pin "1") (pinfunction "1_1") (pintype "passive"))
      (node (ref "MCU") (pin "24") (pinfunction "BPS_24") (pintype "input"))
    )
    (net (code "16") (name "CURRENT_5V") (class "Default")
      (node (ref "IC4") (pin "5") (pinfunction "OUT_5") (pintype "output"))
      (node (ref "MCU") (pin "20") (pinfunction "CURRENT_5V_20") (pintype "input"))
    )
    (net (code "17") (name "CURRENT_SERVO") (class "Default")
      (node (ref "IC5") (pin "5") (pinfunction "OUT_5") (pintype "output"))
      (node (ref "MCU") (pin "21") (pinfunction "CURRENT_SERVO_21") (pintype "input"))
    )
    (net (code "18") (name "DEBUG_LED") (class "Default")
      (node (ref "MCU") (pin "37") (pinfunction "DEBUG_LED_37") (pintype "output"))
      (node (ref "U4") (pin "G") (pinfunction "G_G") (pintype "passive"))
    )
    (net (code "19") (name "DRV_DISPLAY") (class "Default")
      (node (ref "IC8") (pin "13") (pinfunction "LED6_13") (pintype "output"))
      (node (ref "J7") (pin "9") (pinfunction "9_9") (pintype "passive"))
    )
    (net (code "20") (name "DRV_ERW_1") (class "Default")
      (node (ref "IC8") (pin "9") (pinfunction "LED3_9") (pintype "output"))
      (node (ref "J18") (pin "4") (pinfunction "4_4") (pintype "passive"))
    )
    (net (code "21") (name "DRV_ERW_2") (class "Default")
      (node (ref "IC8") (pin "8") (pinfunction "LED2_8") (pintype "output"))
      (node (ref "J18") (pin "3") (pinfunction "3_3") (pintype "passive"))
    )
    (net (code "22") (name "DRV_ERW_3") (class "Default")
      (node (ref "IC8") (pin "14") (pinfunction "LED7_14") (pintype "output"))
      (node (ref "J18") (pin "2") (pinfunction "2_2") (pintype "passive"))
    )
    (net (code "23") (name "DRV_KANTLED_L") (class "Default")
      (node (ref "IC8") (pin "6") (pinfunction "LED0_6") (pintype "output"))
      (node (ref "R10") (pin "2") (pinfunction "2_2") (pintype "passive"))
    )
    (net (code "24") (name "DRV_KANTLED_R") (class "Default")
      (node (ref "IC8") (pin "7") (pinfunction "LED1_7") (pintype "output"))
      (node (ref "R13") (pin "1") (pinfunction "1_1") (pintype "passive"))
    )
    (net (code "25") (name "DRV_LINE_L") (class "Default")
      (node (ref "IC8") (pin "11") (pinfunction "LED4_11") (pintype "output"))
      (node (ref "R17") (pin "2") (pinfunction "2_2") (pintype "passive"))
    )
    (net (code "26") (name "DRV_LINE_R") (class "Default")
      (node (ref "IC8") (pin "12") (pinfunction "LED5_12") (pintype "output"))
      (node (ref "R16") (pin "2") (pinfunction "2_2") (pintype "passive"))
    )
    (net (code "27") (name "ENA_AUDIO") (class "Default")
      (node (ref "IC10") (pin "12") (pinfunction "SHND_12") (pintype "input"))
      (node (ref "IC7") (pin "7") (pinfunction "IO3_7") (pintype "bidirectional"))
    )
    (net (code "28") (name "ENA_ERW_1") (class "Default")
      (node (ref "IC7") (pin "9") (pinfunction "IO4_9") (pintype "bidirectional"))
      (node (ref "J19") (pin "4") (pinfunction "4_4") (pintype "passive"))
    )
    (net (code "29") (name "ENA_ERW_2") (class "Default")
      (node (ref "IC7") (pin "10") (pinfunction "IO5_10") (pintype "bidirectional"))
      (node (ref "J19") (pin "3") (pinfunction "3_3") (pintype "passive"))
    )
    (net (code "30") (name "FERNBED") (class "Default")
      (node (ref "IC9") (pin "1") (pinfunction "OUT_1") (pintype "output"))
      (node (ref "MCU") (pin "25") (pinfunction "FERNBED_25") (pintype "input"))
    )
    (net (code "31") (name "GND") (class "Default")
      (node (ref "C1") (pin "-") (pinfunction "-_-") (pintype "passive"))
      (node (ref "C10") (pin "-") (pinfunction "-_-") (pintype "passive"))
      (node (ref "C11") (pin "2") (pinfunction "2_2") (pintype "passive"))
      (node (ref "C12") (pin "2") (pinfunction "2_2") (pintype "passive"))
      (node (ref "C13") (pin "2") (pinfunction "2_2") (pintype "passive"))
      (node (ref "C14") (pin "-") (pinfunction "-_-") (pintype "passive"))
      (node (ref "C15") (pin "2") (pinfunction "2_2") (pintype "passive"))
      (node (ref "C16") (pin "2") (pinfunction "2_2") (pintype "passive"))
      (node (ref "C17") (pin "2") (pinfunction "2_2") (pintype "passive"))
      (node (ref "C18") (pin "2") (pinfunction "2_2") (pintype "passive"))
      (node (ref "C19") (pin "2") (pinfunction "2_2") (pintype "passive"))
      (node (ref "C2") (pin "2") (pinfunction "2_2") (pintype "passive"))
      (node (ref "C20") (pin "2") (pinfunction "2_2") (pintype "passive"))
      (node (ref "C25") (pin "2") (pinfunction "2_2") (pintype "passive"))
      (node (ref "C26") (pin "-") (pinfunction "-_-") (pintype "passive"))
      (node (ref "C3") (pin "-") (pinfunction "-_-") (pintype "passive"))
      (node (ref "C5") (pin "-") (pinfunction "-_-") (pintype "passive"))
      (node (ref "C6") (pin "2") (pinfunction "2_2") (pintype "passive"))
      (node (ref "C7") (pin "-") (pinfunction "-_-") (pintype "passive"))
      (node (ref "C8") (pin "-") (pinfunction "-_-") (pintype "passive"))
      (node (ref "C9") (pin "2") (pinfunction "2_2") (pintype "passive"))
      (node (ref "D3") (pin "A") (pinfunction "A_A") (pintype "passive"))
      (node (ref "D4") (pin "A") (pinfunction "A_A") (pintype "passive"))
      (node (ref "IC1") (pin "3") (pinfunction "GND_3") (pintype "power_in"))
      (node (ref "IC1") (pin "5") (pinfunction "EN_5") (pintype "input"))
      (node (ref "IC1") (pin "6") (pinfunction "GND_6") (pintype "power_in"))
      (node (ref "IC10") (pin "15") (pinfunction "PGND1_15") (pintype "power_in"))
      (node (ref "IC10") (pin "2") (pinfunction "PGND_2") (pintype "power_in"))
      (node (ref "IC2") (pin "3") (pinfunction "GND_3") (pintype "power_in"))
      (node (ref "IC2") (pin "5") (pinfunction "EN_5") (pintype "input"))
      (node (ref "IC2") (pin "6") (pinfunction "GND_6") (pintype "power_in"))
      (node (ref "IC3") (pin "GND") (pinfunction "GND_GND") (pintype "bidirectional"))
      (node (ref "IC4") (pin "2") (pinfunction "GND_2") (pintype "power_in"))
      (node (ref "IC4") (pin "3") (pinfunction "REF2_3") (pintype "input"))
      (node (ref "IC4") (pin "7") (pinfunction "REF1_7") (pintype "input"))
      (node (ref "IC5") (pin "2") (pinfunction "GND_2") (pintype "power_in"))
      (node (ref "IC5") (pin "3") (pinfunction "REF2_3") (pintype "input"))
      (node (ref "IC5") (pin "7") (pinfunction "REF1_7") (pintype "input"))
      (node (ref "IC6") (pin "10") (pinfunction "VSS_10") (pintype "power_in"))
      (node (ref "IC6") (pin "15") (pinfunction "OE_15") (pintype "input"))
      (node (ref "IC6") (pin "16") (pinfunction "A5_16") (pintype "input"))
      (node (ref "IC6") (pin "17") (pinfunction "A6_17") (pintype "input"))
      (node (ref "IC6") (pin "2") (pinfunction "A1_2") (pintype "input"))
      (node (ref "IC6") (pin "4") (pinfunction "A3_4") (pintype "input"))
      (node (ref "IC7") (pin "1") (pinfunction "A0_1") (pintype "input"))
      (node (ref "IC7") (pin "2") (pinfunction "A1_2") (pintype "input"))
      (node (ref "IC7") (pin "3") (pinfunction "A2_3") (pintype "input"))
      (node (ref "IC7") (pin "8") (pinfunction "VSS_8") (pintype "power_in"))
      (node (ref "IC8") (pin "10") (pinfunction "VSS_10") (pintype "power_in"))
      (node (ref "IC8") (pin "15") (pinfunction "OE_15") (pintype "input"))
      (node (ref "IC8") (pin "16") (pinfunction "A5_16") (pintype "input"))
      (node (ref "IC8") (pin "17") (pinfunction "A6_17") (pintype "input"))
      (node (ref "IC8") (pin "2") (pinfunction "A1_2") (pintype "input"))
      (node (ref "IC9") (pin "3") (pinfunction "GND_3") (pintype "power_in"))
      (node (ref "J1") (pin "2") (pinfunction "2_2") (pintype "passive"))
      (node (ref "J10") (pin "1") (pinfunction "1_1") (pintype "passive"))
      (node (ref "J11") (pin "1") (pinfunction "1_1") (pintype "passive"))
      (node (ref "J12") (pin "1") (pinfunction "1_1") (pintype "passive"))
      (node (ref "J13") (pin "1") (pinfunction "1_1") (pintype "passive"))
      (node (ref "J14") (pin "1") (pinfunction "1_1") (pintype "passive"))
      (node (ref "J15") (pin "1") (pinfunction "1_1") (pintype "passive"))
      (node (ref "J16") (pin "1") (pinfunction "1_1") (pintype "passive"))
      (node (ref "J16") (pin "2") (pinfunction "2_2") (pintype "passive"))
      (node (ref "J18") (pin "1") (pinfunction "1_1") (pintype "passive"))
      (node (ref "J19") (pin "1") (pinfunction "1_1") (pintype "passive"))
      (node (ref "J2") (pin "3") (pinfunction "3_3") (pintype "passive"))
      (node (ref "J2") (pin "4") (pinfunction "4_4") (pintype "passive"))
      (node (ref "J3") (pin "1") (pinfunction "1_1") (pintype "passive"))
      (node (ref "J4") (pin "1") (pinfunction "1_1") (pintype "passive"))
      (node (ref "J5") (pin "2") (pinfunction "2_2") (pintype "passive"))
      (node (ref "J6") (pin "1") (pinfunction "1_1") (pintype "passive"))
      (node (ref "J7") (pin "2") (pinfunction "2_2") (pintype "passive"))
      (node (ref "J8") (pin "2") (pinfunction "2_2") (pintype "passive"))
      (node (ref "J9") (pin "2") (pinfunction "2_2") (pintype "passive"))
      (node (ref "LED1") (pin "K") (pinfunction "C_K") (pintype "passive"))
      (node (ref "LED2") (pin "K") (pinfunction "C_K") (pintype "passive"))
      (node (ref "LED3") (pin "K") (pinfunction "C_K") (pintype "passive"))
      (node (ref "MCU") (pin "1") (pinfunction "GND_1") (pintype "power_in"))
      (node (ref "R6") (pin "1") (pinfunction "1_1") (pintype "passive"))
      (node (ref "S1") (pin "1") (pinfunction "1_1") (pintype "passive"))
      (node (ref "S2") (pin "1") (pinfunction "1_1") (pintype "passive"))
      (node (ref "U$10") (pin "GND") (pinfunction "GND_GND") (pintype "power_in"))
      (node (ref "U1") (pin "3") (pinfunction "S_3") (pintype "passive"))
      (node (ref "U4") (pin "S") (pinfunction "S_S") (pintype "passive"))
      (node (ref "X2") (pin "P$8") (pinfunction "1_P$8") (pintype "passive"))
      (node (ref "X3") (pin "P$8") (pinfunction "1_P$8") (pintype "passive"))
      (node (ref "X4") (pin "P$6") (pinfunction "1_P$6") (pintype "passive"))
      (node (ref "X5") (pin "P$8") (pinfunction "1_P$8") (pintype "passive"))
    )
    (net (code "32") (name "GPIO1") (class "Default")
      (node (ref "J8") (pin "6") (pinfunction "6_6") (pintype "passive"))
      (node (ref "J9") (pin "6") (pinfunction "6_6") (pintype "passive"))
      (node (ref "MCU") (pin "42") (pinfunction "GPIO1_42") (pintype "bidirectional"))
    )
    (net (code "33") (name "GPIO2") (class "Default")
      (node (ref "J8") (pin "7") (pinfunction "7_7") (pintype "passive"))
      (node (ref "MCU") (pin "43") (pinfunction "GPIO2_43") (pintype "bidirectional"))
    )
    (net (code "34") (name "IMU_RST") (class "Default")
      (node (ref "IC7") (pin "12") (pinfunction "IO7_12") (pintype "bidirectional"))
      (node (ref "J19") (pin "2") (pinfunction "2_2") (pintype "passive"))
      (node (ref "U$10") (pin "RST") (pinfunction "RST_RST") (pintype "input"))
    )
    (net (code "35") (name "KANTE_L") (class "Default")
      (node (ref "MCU") (pin "29") (pinfunction "KANTE_L_29") (pintype "input"))
      (node (ref "R11") (pin "1") (pinfunction "1_1") (pintype "passive"))
      (node (ref "X2") (pin "P$7") (pinfunction "1_P$7") (pintype "passive"))
    )
    (net (code "36") (name "KANTE_R") (class "Default")
      (node (ref "MCU") (pin "28") (pinfunction "KANTE_R_28") (pintype "input"))
      (node (ref "R12") (pin "2") (pinfunction "2_2") (pintype "passive"))
      (node (ref "X3") (pin "P$7") (pinfunction "1_P$7") (pintype "passive"))
    )
    (net (code "37") (name "LINE_IN_L") (class "Default")
      (node (ref "J22") (pin "2") (pinfunction "2_2") (pintype "passive"))
      (node (ref "R41") (pin "1") (pinfunction "A_1") (pintype "passive"))
    )
    (net (code "38") (name "LINE_IN_R") (class "Default")
      (node (ref "J22") (pin "3") (pinfunction "3_3") (pintype "passive"))
      (node (ref "R42") (pin "1") (pinfunction "A_1") (pintype "passive"))
    )
    (net (code "39") (name "LINIE_L") (class "Default")
      (node (ref "MCU") (pin "36") (pinfunction "LINIE_L_36") (pintype "input"))
      (node (ref "R15") (pin "1") (pinfunction "1_1") (pintype "passive"))
      (node (ref "X4") (pin "P$4") (pinfunction "1_P$4") (pintype "passive"))
    )
    (net (code "40") (name "LINIE_R") (class "Default")
      (node (ref "MCU") (pin "35") (pinfunction "LINIE_R_35") (pintype "input"))
      (node (ref "R14") (pin "1") (pinfunction "1_1") (pintype "passive"))
      (node (ref "X4") (pin "P$5") (pinfunction "1_P$5") (pintype "passive"))
    )
    (net (code "41") (name "MCTRL_RESET") (class "Default")
      (node (ref "C11") (pin "1") (pinfunction "1_1") (pintype "passive"))
      (node (ref "IC7") (pin "11") (pinfunction "IO6_11") (pintype "bidirectional"))
      (node (ref "R18") (pin "2") (pinfunction "2_2") (pintype "passive"))
      (node (ref "X5") (pin "P$7") (pinfunction "1_P$7") (pintype "passive"))
    )
    (net (code "42") (name "Net-(C21-Pad1)") (class "Default")
      (node (ref "C21") (pin "1") (pinfunction "1_1") (pintype "passive"))
      (node (ref "R43") (pin "2") (pinfunction "2_2") (pintype "passive"))
    )
    (net (code "43") (name "Net-(C22-Pad1)") (class "Default")
      (node (ref "C22") (pin "1") (pinfunction "1_1") (pintype "passive"))
      (node (ref "R44") (pin "2") (pinfunction "2_2") (pintype "passive"))
    )
    (net (code "44") (name "Net-(D1-PadA)") (class "Default")
      (node (ref "D1") (pin "A") (pinfunction "A_A") (pintype "passive"))
      (node (ref "D2") (pin "C") (pinfunction "C_C") (pintype "passive"))
      (node (ref "R1") (pin "2") (pinfunction "2_2") (pintype "passive"))
      (node (ref "R2") (pin "1") (pinfunction "1_1") (pintype "passive"))
      (node (ref "R3") (pin "2") (pinfunction "2_2") (pintype "passive"))
    )
    (net (code "45") (name "Net-(D5-A)") (class "Default")
      (node (ref "D5") (pin "1") (pinfunction "A_1") (pintype "passive"))
      (node (ref "X2") (pin "P$4") (pinfunction "1_P$4") (pintype "passive"))
    )
    (net (code "46") (name "Net-(D6-A)") (class "Default")
      (node (ref "D6") (pin "1") (pinfunction "A_1") (pintype "passive"))
      (node (ref "X2") (pin "P$5") (pinfunction "1_P$5") (pintype "passive"))
    )
    (net (code "47") (name "Net-(D7-A)") (class "Default")
      (node (ref "D7") (pin "1") (pinfunction "A_1") (pintype "passive"))
      (node (ref "X3") (pin "P$4") (pinfunction "1_P$4") (pintype "passive"))
    )
    (net (code "48") (name "Net-(IC1-FB)") (class "Default")
      (node (ref "C4") (pin "2") (pinfunction "2_2") (pintype "passive"))
      (node (ref "IC1") (pin "4") (pinfunction "FB_4") (pintype "input"))
      (node (ref "R5") (pin "1") (pinfunction "1_1") (pintype "passive"))
      (node (ref "R6") (pin "2") (pinfunction "2_2") (pintype "passive"))
    )
    (net (code "49") (name "Net-(IC1-OUT)") (class "Default")
      (node (ref "D3") (pin "C") (pinfunction "C_C") (pintype "passive"))
      (node (ref "IC1") (pin "2") (pinfunction "OUT_2") (pintype "output"))
      (node (ref "L1") (pin "1") (pinfunction "1_1") (pintype "passive"))
    )
    (net (code "50") (name "Net-(IC2-FB)") (class "Default")
      (node (ref "C7") (pin "+") (pinfunction "+_+") (pintype "passive"))
      (node (ref "IC2") (pin "4") (pinfunction "FB_4") (pintype "input"))
      (node (ref "L2") (pin "2") (pinfunction "2_2") (pintype "passive"))
      (node (ref "L3") (pin "1") (pinfunction "1_1") (pintype "passive"))
    )
    (net (code "51") (name "Net-(IC2-OUT)") (class "Default")
      (node (ref "D4") (pin "C") (pinfunction "C_C") (pintype "passive"))
      (node (ref "IC2") (pin "2") (pinfunction "OUT_2") (pintype "output"))
      (node (ref "L2") (pin "1") (pinfunction "1_1") (pintype "passive"))
    )
    (net (code "52") (name "Net-(IC6-LED0)") (class "Default")
      (node (ref "IC6") (pin "6") (pinfunction "LED0_6") (pintype "output"))
      (node (ref "LED12") (pin "K") (pinfunction "C_K") (pintype "passive"))
    )
    (net (code "53") (name "Net-(IC6-LED1)") (class "Default")
      (node (ref "IC6") (pin "7") (pinfunction "LED1_7") (pintype "output"))
      (node (ref "LED11") (pin "K") (pinfunction "C_K") (pintype "passive"))
    )
    (net (code "54") (name "Net-(IC6-LED2)") (class "Default")
      (node (ref "IC6") (pin "8") (pinfunction "LED2_8") (pintype "output"))
      (node (ref "LED10") (pin "K") (pinfunction "C_K") (pintype "passive"))
    )
    (net (code "55") (name "Net-(IC6-LED3)") (class "Default")
      (node (ref "IC6") (pin "9") (pinfunction "LED3_9") (pintype "output"))
      (node (ref "LED9") (pin "K") (pinfunction "C_K") (pintype "passive"))
    )
    (net (code "56") (name "Net-(IC6-LED4)") (class "Default")
      (node (ref "IC6") (pin "11") (pinfunction "LED4_11") (pintype "output"))
      (node (ref "LED8") (pin "K") (pinfunction "C_K") (pintype "passive"))
    )
    (net (code "57") (name "Net-(IC6-LED5)") (class "Default")
      (node (ref "IC6") (pin "12") (pinfunction "LED5_12") (pintype "output"))
      (node (ref "LED7") (pin "K") (pinfunction "C_K") (pintype "passive"))
    )
    (net (code "58") (name "Net-(IC6-LED6)") (class "Default")
      (node (ref "IC6") (pin "13") (pinfunction "LED6_13") (pintype "output"))
      (node (ref "LED6") (pin "K") (pinfunction "C_K") (pintype "passive"))
    )
    (net (code "59") (name "Net-(IC6-LED7)") (class "Default")
      (node (ref "IC6") (pin "14") (pinfunction "LED7_14") (pintype "output"))
      (node (ref "LED5") (pin "K") (pinfunction "C_K") (pintype "passive"))
    )
    (net (code "60") (name "Net-(IC10-+OUT_L)") (class "Default")
      (node (ref "IC10") (pin "1") (pinfunction "+OUT_L_1") (pintype "output"))
      (node (ref "J21") (pin "2") (pinfunction "2_2") (pintype "passive"))
    )
    (net (code "61") (name "Net-(IC10-+OUT_R)") (class "Default")
      (node (ref "IC10") (pin "16") (pinfunction "+OUT_R_16") (pintype "output"))
      (node (ref "J20") (pin "2") (pinfunction "2_2") (pintype "passive"))
    )
    (net (code "62") (name "Net-(IC10--OUT_L)") (class "Default")
      (node (ref "IC10") (pin "3") (pinfunction "-OUT_L_3") (pintype "output"))
      (node (ref "J21") (pin "1") (pinfunction "1_1") (pintype "passive"))
    )
    (net (code "63") (name "Net-(IC10--OUT_R)") (class "Default")
      (node (ref "IC10") (pin "14") (pinfunction "-OUT_R_14") (pintype "output"))
      (node (ref "J20") (pin "1") (pinfunction "1_1") (pintype "passive"))
    )
    (net (code "64") (name "Net-(IC10-INL)") (class "Default")
      (node (ref "IC10") (pin "7") (pinfunction "INL_7") (pintype "input"))
      (node (ref "R43") (pin "1") (pinfunction "1_1") (pintype "passive"))
    )
    (net (code "65") (name "Net-(IC10-INR)") (class "Default")
      (node (ref "IC10") (pin "10") (pinfunction "INR_10") (pintype "input"))
      (node (ref "R44") (pin "1") (pinfunction "1_1") (pintype "passive"))
    )
    (net (code "66") (name "Net-(IC10-VREF)") (class "Default")
      (node (ref "C24") (pin "1") (pinfunction "1_1") (pintype "passive"))
      (node (ref "IC10") (pin "8") (pinfunction "VREF_8") (pintype "passive"))
    )
    (net (code "67") (name "Net-(LED1-PadA)") (class "Default")
      (node (ref "LED1") (pin "A") (pinfunction "A_A") (pintype "passive"))
      (node (ref "R7") (pin "2") (pinfunction "2_2") (pintype "passive"))
    )
    (net (code "68") (name "Net-(LED2-PadA)") (class "Default")
      (node (ref "LED2") (pin "A") (pinfunction "A_A") (pintype "passive"))
      (node (ref "R8") (pin "1") (pinfunction "1_1") (pintype "passive"))
    )
    (net (code "69") (name "Net-(LED3-PadA)") (class "Default")
      (node (ref "LED3") (pin "A") (pinfunction "A_A") (pintype "passive"))
      (node (ref "R9") (pin "1") (pinfunction "1_1") (pintype "passive"))
    )
    (net (code "70") (name "Net-(LED4-C)") (class "Default")
      (node (ref "LED4") (pin "K") (pinfunction "C_K") (pintype "passive"))
      (node (ref "U4") (pin "D") (pinfunction "D_D") (pintype "passive"))
    )
    (net (code "71") (name "Net-(LED4-PadA)") (class "Default")
      (node (ref "LED4") (pin "A") (pinfunction "A_A") (pintype "passive"))
      (node (ref "R27") (pin "1") (pinfunction "1_1") (pintype "passive"))
    )
    (net (code "72") (name "Net-(LED5-PadA)") (class "Default")
      (node (ref "LED5") (pin "A") (pinfunction "A_A") (pintype "passive"))
      (node (ref "R29") (pin "2") (pinfunction "2_2") (pintype "passive"))
    )
    (net (code "73") (name "Net-(LED6-PadA)") (class "Default")
      (node (ref "LED6") (pin "A") (pinfunction "A_A") (pintype "passive"))
      (node (ref "R30") (pin "2") (pinfunction "2_2") (pintype "passive"))
    )
    (net (code "74") (name "Net-(LED7-PadA)") (class "Default")
      (node (ref "LED7") (pin "A") (pinfunction "A_A") (pintype "passive"))
      (node (ref "R31") (pin "2") (pinfunction "2_2") (pintype "passive"))
    )
    (net (code "75") (name "Net-(LED8-PadA)") (class "Default")
      (node (ref "LED8") (pin "A") (pinfunction "A_A") (pintype "passive"))
      (node (ref "R32") (pin "2") (pinfunction "2_2") (pintype "passive"))
    )
    (net (code "76") (name "Net-(LED9-PadA)") (class "Default")
      (node (ref "LED9") (pin "A") (pinfunction "A_A") (pintype "passive"))
      (node (ref "R33") (pin "2") (pinfunction "2_2") (pintype "passive"))
    )
    (net (code "77") (name "Net-(LED10-PadA)") (class "Default")
      (node (ref "LED10") (pin "A") (pinfunction "A_A") (pintype "passive"))
      (node (ref "R34") (pin "2") (pinfunction "2_2") (pintype "passive"))
    )
    (net (code "78") (name "Net-(LED11-PadA)") (class "Default")
      (node (ref "LED11") (pin "A") (pinfunction "A_A") (pintype "passive"))
      (node (ref "R35") (pin "2") (pinfunction "2_2") (pintype "passive"))
    )
    (net (code "79") (name "Net-(LED12-PadA)") (class "Default")
      (node (ref "LED12") (pin "A") (pinfunction "A_A") (pintype "passive"))
      (node (ref "R36") (pin "2") (pinfunction "2_2") (pintype "passive"))
    )
    (net (code "80") (name "Net-(R41-S)") (class "Default")
      (node (ref "C21") (pin "2") (pinfunction "2_2") (pintype "passive"))
      (node (ref "R41") (pin "2") (pinfunction "S_2") (pintype "passive"))
    )
    (net (code "81") (name "Net-(R42-S)") (class "Default")
      (node (ref "C22") (pin "2") (pinfunction "2_2") (pintype "passive"))
      (node (ref "R42") (pin "2") (pinfunction "S_2") (pintype "passive"))
    )
    (net (code "82") (name "Net-(S1-2)") (class "Default")
      (node (ref "R18") (pin "1") (pinfunction "1_1") (pintype "passive"))
      (node (ref "S1") (pin "3") (pinfunction "2_3") (pintype "passive"))
    )
    (net (code "83") (name "Net-(S2-2)") (class "Default")
      (node (ref "R28") (pin "1") (pinfunction "1_1") (pintype "passive"))
      (node (ref "S2") (pin "3") (pinfunction "2_3") (pintype "passive"))
    )
    (net (code "84") (name "Net-(U1-G)") (class "Default")
      (node (ref "R4") (pin "1") (pinfunction "1_1") (pintype "passive"))
      (node (ref "U1") (pin "1") (pinfunction "G_1") (pintype "passive"))
    )
    (net (code "85") (name "Net-(X2F-1)") (class "Default")
      (node (ref "R10") (pin "1") (pinfunction "1_1") (pintype "passive"))
      (node (ref "X2") (pin "P$6") (pinfunction "1_P$6") (pintype "passive"))
    )
    (net (code "86") (name "Net-(X3F-1)") (class "Default")
      (node (ref "R13") (pin "2") (pinfunction "2_2") (pintype "passive"))
      (node (ref "X3") (pin "P$6") (pinfunction "1_P$6") (pintype "passive"))
    )
    (net (code "87") (name "Net-(X4B-1)") (class "Default")
      (node (ref "R17") (pin "1") (pinfunction "1_1") (pintype "passive"))
      (node (ref "X4") (pin "P$2") (pinfunction "1_P$2") (pintype "passive"))
    )
    (net (code "88") (name "Net-(X4C-1)") (class "Default")
      (node (ref "R16") (pin "1") (pinfunction "1_1") (pintype "passive"))
      (node (ref "X4") (pin "P$3") (pinfunction "1_P$3") (pintype "passive"))
    )
    (net (code "89") (name "RESET") (class "Default")
      (node (ref "C15") (pin "1") (pinfunction "1_1") (pintype "passive"))
      (node (ref "MCU") (pin "34") (pinfunction "RESET_34") (pintype "input"))
      (node (ref "R28") (pin "2") (pinfunction "2_2") (pintype "passive"))
    )
    (net (code "90") (name "RX1") (class "Default")
      (node (ref "J12") (pin "4") (pinfunction "4_4") (pintype "passive"))
      (node (ref "MCU") (pin "26") (pinfunction "RX1_26") (pintype "input"))
      (node (ref "X5") (pin "P$5") (pinfunction "1_P$5") (pintype "passive"))
    )
    (net (code "91") (name "RX2") (class "Default")
      (node (ref "MCU") (pin "22") (pinfunction "RX2_22") (pintype "input"))
      (node (ref "X5") (pin "P$3") (pinfunction "1_P$3") (pintype "passive"))
    )
    (net (code "92") (name "SCHRANKE_SHDN") (class "Default")
      (node (ref "D6") (pin "2") (pinfunction "C_2") (pintype "passive"))
      (node (ref "IC7") (pin "5") (pinfunction "IO1_5") (pintype "bidirectional"))
    )
    (net (code "93") (name "SCL1") (class "Default")
      (node (ref "J4") (pin "4") (pinfunction "4_4") (pintype "passive"))
      (node (ref "MCU") (pin "41") (pinfunction "SCL1_41") (pintype "output"))
      (node (ref "R22") (pin "1") (pinfunction "1_1") (pintype "passive"))
      (node (ref "U2") (pin "S") (pinfunction "S_S") (pintype "passive"))
    )
    (net (code "94") (name "SCL1_5V") (class "Default")
      (node (ref "IC6") (pin "18") (pinfunction "SCL_18") (pintype "input"))
      (node (ref "IC7") (pin "14") (pinfunction "SCL_14") (pintype "input"))
      (node (ref "IC8") (pin "18") (pinfunction "SCL_18") (pintype "input"))
      (node (ref "J3") (pin "4") (pinfunction "4_4") (pintype "passive"))
      (node (ref "R24") (pin "1") (pinfunction "1_1") (pintype "passive"))
      (node (ref "U2") (pin "D") (pinfunction "D_D") (pintype "passive"))
      (node (ref "X2") (pin "P$3") (pinfunction "1_P$3") (pintype "passive"))
      (node (ref "X3") (pin "P$3") (pinfunction "1_P$3") (pintype "passive"))
    )
    (net (code "95") (name "SCL2") (class "Default")
      (node (ref "J10") (pin "3") (pinfunction "3_3") (pintype "passive"))
      (node (ref "MCU") (pin "39") (pinfunction "SCL2_39") (pintype "output"))
      (node (ref "R26") (pin "1") (pinfunction "1_1") (pintype "passive"))
      (node (ref "U$10") (pin "SCL") (pinfunction "SCL_SCL") (pintype "input"))
    )
    (net (code "96") (name "SCL3") (class "Default")
      (node (ref "J11") (pin "3") (pinfunction "3_3") (pintype "passive"))
      (node (ref "MCU") (pin "6") (pinfunction "SCL3_6") (pintype "output"))
    )
    (net (code "97") (name "SDA1") (class "Default")
      (node (ref "J4") (pin "3") (pinfunction "3_3") (pintype "passive"))
      (node (ref "MCU") (pin "40") (pinfunction "SDA1_40") (pintype "bidirectional"))
      (node (ref "R21") (pin "1") (pinfunction "1_1") (pintype "passive"))
      (node (ref "U3") (pin "S") (pinfunction "S_S") (pintype "passive"))
    )
    (net (code "98") (name "SDA1_5V") (class "Default")
      (node (ref "IC6") (pin "19") (pinfunction "SDA_19") (pintype "bidirectional"))
      (node (ref "IC7") (pin "15") (pinfunction "SDA_15") (pintype "bidirectional"))
      (node (ref "IC8") (pin "19") (pinfunction "SDA_19") (pintype "bidirectional"))
      (node (ref "J3") (pin "3") (pinfunction "3_3") (pintype "passive"))
      (node (ref "R23") (pin "1") (pinfunction "1_1") (pintype "passive"))
      (node (ref "U3") (pin "D") (pinfunction "D_D") (pintype "passive"))
      (node (ref "X2") (pin "P$2") (pinfunction "1_P$2") (pintype "passive"))
      (node (ref "X3") (pin "P$2") (pinfunction "1_P$2") (pintype "passive"))
    )
    (net (code "99") (name "SDA2") (class "Default")
      (node (ref "J10") (pin "4") (pinfunction "4_4") (pintype "passive"))
      (node (ref "MCU") (pin "38") (pinfunction "SDA2_38") (pintype "bidirectional"))
      (node (ref "R25") (pin "1") (pinfunction "1_1") (pintype "passive"))
      (node (ref "U$10") (pin "SDA") (pinfunction "SDA_SDA") (pintype "bidirectional"))
    )
    (net (code "100") (name "SDA3") (class "Default")
      (node (ref "J11") (pin "4") (pinfunction "4_4") (pintype "passive"))
      (node (ref "MCU") (pin "7") (pinfunction "SDA3_7") (pintype "bidirectional"))
    )
    (net (code "101") (name "SERVO1_FB") (class "Default")
      (node (ref "J6") (pin "4") (pinfunction "4_4") (pintype "passive"))
      (node (ref "MCU") (pin "16") (pinfunction "SERVO1_FB_16") (pintype "input"))
    )
    (net (code "102") (name "SERVO1_PWM") (class "Default")
      (node (ref "J6") (pin "3") (pinfunction "3_3") (pintype "passive"))
      (node (ref "MCU") (pin "8") (pinfunction "SERVO1_PWM_8") (pintype "output"))
      (node (ref "R37") (pin "1") (pinfunction "1_1") (pintype "passive"))
    )
    (net (code "103") (name "SERVO2_FB") (class "Default")
      (node (ref "J13") (pin "4") (pinfunction "4_4") (pintype "passive"))
      (node (ref "MCU") (pin "17") (pinfunction "SERVO2_FB_17") (pintype "input"))
    )
    (net (code "104") (name "SERVO2_PWM") (class "Default")
      (node (ref "J13") (pin "3") (pinfunction "3_3") (pintype "passive"))
      (node (ref "MCU") (pin "9") (pinfunction "SERVO2_PWM_9") (pintype "output"))
      (node (ref "R38") (pin "1") (pinfunction "1_1") (pintype "passive"))
    )
    (net (code "105") (name "SERVO3_FB") (class "Default")
      (node (ref "J14") (pin "4") (pinfunction "4_4") (pintype "passive"))
      (node (ref "MCU") (pin "5") (pinfunction "SERVO3_FB_5") (pintype "input"))
    )
    (net (code "106") (name "SERVO3_PWM") (class "Default")
      (node (ref "J14") (pin "3") (pinfunction "3_3") (pintype "passive"))
      (node (ref "MCU") (pin "18") (pinfunction "SERVO3_PWM_18") (pintype "bidirectional"))
      (node (ref "R39") (pin "1") (pinfunction "1_1") (pintype "passive"))
    )
    (net (code "107") (name "SERVO4_PWM") (class "Default")
      (node (ref "J15") (pin "3") (pinfunction "3_3") (pintype "passive"))
      (node (ref "MCU") (pin "19") (pinfunction "SERVO4_PWM_19") (pintype "bidirectional"))
      (node (ref "R40") (pin "1") (pinfunction "1_1") (pintype "passive"))
    )
    (net (code "108") (name "SPI1_CS1") (class "Default")
      (node (ref "J7") (pin "6") (pinfunction "6_6") (pintype "passive"))
      (node (ref "MCU") (pin "12") (pinfunction "SPI1_CS1_12") (pintype "output"))
    )
    (net (code "109") (name "SPI1_CS2") (class "Default")
      (node (ref "J7") (pin "7") (pinfunction "7_7") (pintype "passive"))
      (node (ref "MCU") (pin "11") (pinfunction "SPI1_CS2_11") (pintype "output"))
    )
    (net (code "110") (name "SPI1_CS3") (class "Default")
      (node (ref "J7") (pin "8") (pinfunction "8_8") (pintype "passive"))
      (node (ref "MCU") (pin "10") (pinfunction "SPI1_CS3_10") (pintype "output"))
    )
    (net (code "111") (name "SPI1_MISO") (class "Default")
      (node (ref "J7") (pin "4") (pinfunction "4_4") (pintype "passive"))
      (node (ref "J8") (pin "4") (pinfunction "4_4") (pintype "passive"))
      (node (ref "J9") (pin "4") (pinfunction "4_4") (pintype "passive"))
      (node (ref "MCU") (pin "14") (pinfunction "SPI1_MISO_14") (pintype "input"))
    )
    (net (code "112") (name "SPI1_MOSI") (class "Default")
      (node (ref "J7") (pin "3") (pinfunction "3_3") (pintype "passive"))
      (node (ref "J8") (pin "3") (pinfunction "3_3") (pintype "passive"))
      (node (ref "J9") (pin "3") (pinfunction "3_3") (pintype "passive"))
      (node (ref "MCU") (pin "13") (pinfunction "SPI1_MOSI_13") (pintype "output"))
    )
    (net (code "113") (name "SPI1_SCK") (class "Default")
      (node (ref "J7") (pin "5") (pinfunction "5_5") (pintype "passive"))
      (node (ref "J8") (pin "5") (pinfunction "5_5") (pintype "passive"))
      (node (ref "J9") (pin "5") (pinfunction "5_5") (pintype "passive"))
      (node (ref "MCU") (pin "15") (pinfunction "SPI1_SCK_15") (pintype "output"))
    )
    (net (code "114") (name "SPI2_CS1") (class "Default")
      (node (ref "J16") (pin "4") (pinfunction "4_4") (pintype "passive"))
      (node (ref "MCU") (pin "33") (pinfunction "SPI2_CS1_33") (pintype "output"))
    )
    (net (code "115") (name "SPI2_MISO") (class "Default")
      (node (ref "J16") (pin "8") (pinfunction "8_8") (pintype "passive"))
      (node (ref "MCU") (pin "31") (pinfunction "SPI2_MISO_31") (pintype "input"))
    )
    (net (code "116") (name "SPI2_MOSI") (class "Default")
      (node (ref "J16") (pin "6") (pinfunction "6_6") (pintype "passive"))
      (node (ref "MCU") (pin "32") (pinfunction "SPI2_MOSI_32") (pintype "output"))
    )
    (net (code "117") (name "SPI2_SCK") (class "Default")
      (node (ref "J16") (pin "10") (pinfunction "10_10") (pintype "passive"))
      (node (ref "MCU") (pin "30") (pinfunction "SPI2_SCK_30") (pintype "output"))
    )
    (net (code "118") (name "TX1") (class "Default")
      (node (ref "J12") (pin "3") (pinfunction "3_3") (pintype "passive"))
      (node (ref "MCU") (pin "27") (pinfunction "TX1_27") (pintype "output"))
      (node (ref "X5") (pin "P$6") (pinfunction "1_P$6") (pintype "passive"))
    )
    (net (code "119") (name "TX2") (class "Default")
      (node (ref "MCU") (pin "23") (pinfunction "TX2_23") (pintype "output"))
      (node (ref "X5") (pin "P$4") (pinfunction "1_P$4") (pintype "passive"))
    )
    (net (code "120") (name "VCC_MCU") (class "Default")
      (node (ref "MCU") (pin "3") (pinfunction "VCC_MCU_3") (pintype "power_in"))
    )
    (net (code "121") (name "unconnected-(IC7-~{INT}-Pad13)") (class "Default")
      (node (ref "IC7") (pin "13") (pinfunction "~{INT}_13") (pintype "output"))
    )
    (net (code "122") (name "unconnected-(IC10-MUTE-Pad5)") (class "Default")
      (node (ref "IC10") (pin "5") (pinfunction "MUTE_5") (pintype "input"))
    )
    (net (code "123") (name "unconnected-(IC10-NC-Pad9)") (class "Default")
      (node (ref "IC10") (pin "9") (pinfunction "NC_9") (pintype "no_connect"))
    )
    (net (code "124") (name "unconnected-(MCU-PROGRAM-Pad4)") (class "Default")
      (node (ref "MCU") (pin "4") (pinfunction "PROGRAM_4") (pintype "input"))
    )
    (net (code "125") (name "unconnected-(SW1-S-Pad3)") (class "Default")
      (node (ref "SW1") (pin "3") (pinfunction "S_3") (pintype "passive"))
    )
    (net (code "126") (name "unconnected-(U$10-Pad3V3)") (class "Default")
      (node (ref "U$10") (pin "3V3") (pinfunction "3V3_3V3") (pintype "output"))
    )
    (net (code "127") (name "unconnected-(U$10-PadAINT1)") (class "Default")
      (node (ref "U$10") (pin "AINT1") (pinfunction "AINT1_AINT1") (pintype "output"))
    )
    (net (code "128") (name "unconnected-(U$10-PadAINT2)") (class "Default")
      (node (ref "U$10") (pin "AINT2") (pinfunction "AINT2_AINT2") (pintype "output"))
    )
    (net (code "129") (name "unconnected-(U$10-PadGINT1)") (class "Default")
      (node (ref "U$10") (pin "GINT1") (pinfunction "GINT1_GINT1") (pintype "output"))
    )
    (net (code "130") (name "unconnected-(U$10-PadGINT2)") (class "Default")
      (node (ref "U$10") (pin "GINT2") (pinfunction "GINT2_GINT2") (pintype "output"))
    )
    (net (code "131") (name "unconnected-(X3E-1-PadP$5)") (class "Default")
      (node (ref "X3") (pin "P$5") (pinfunction "1_P$5") (pintype "passive"))
    )
  )
)
